# ADCSHub.net
KiCad netlist of a schematic drawn in Altium Designer
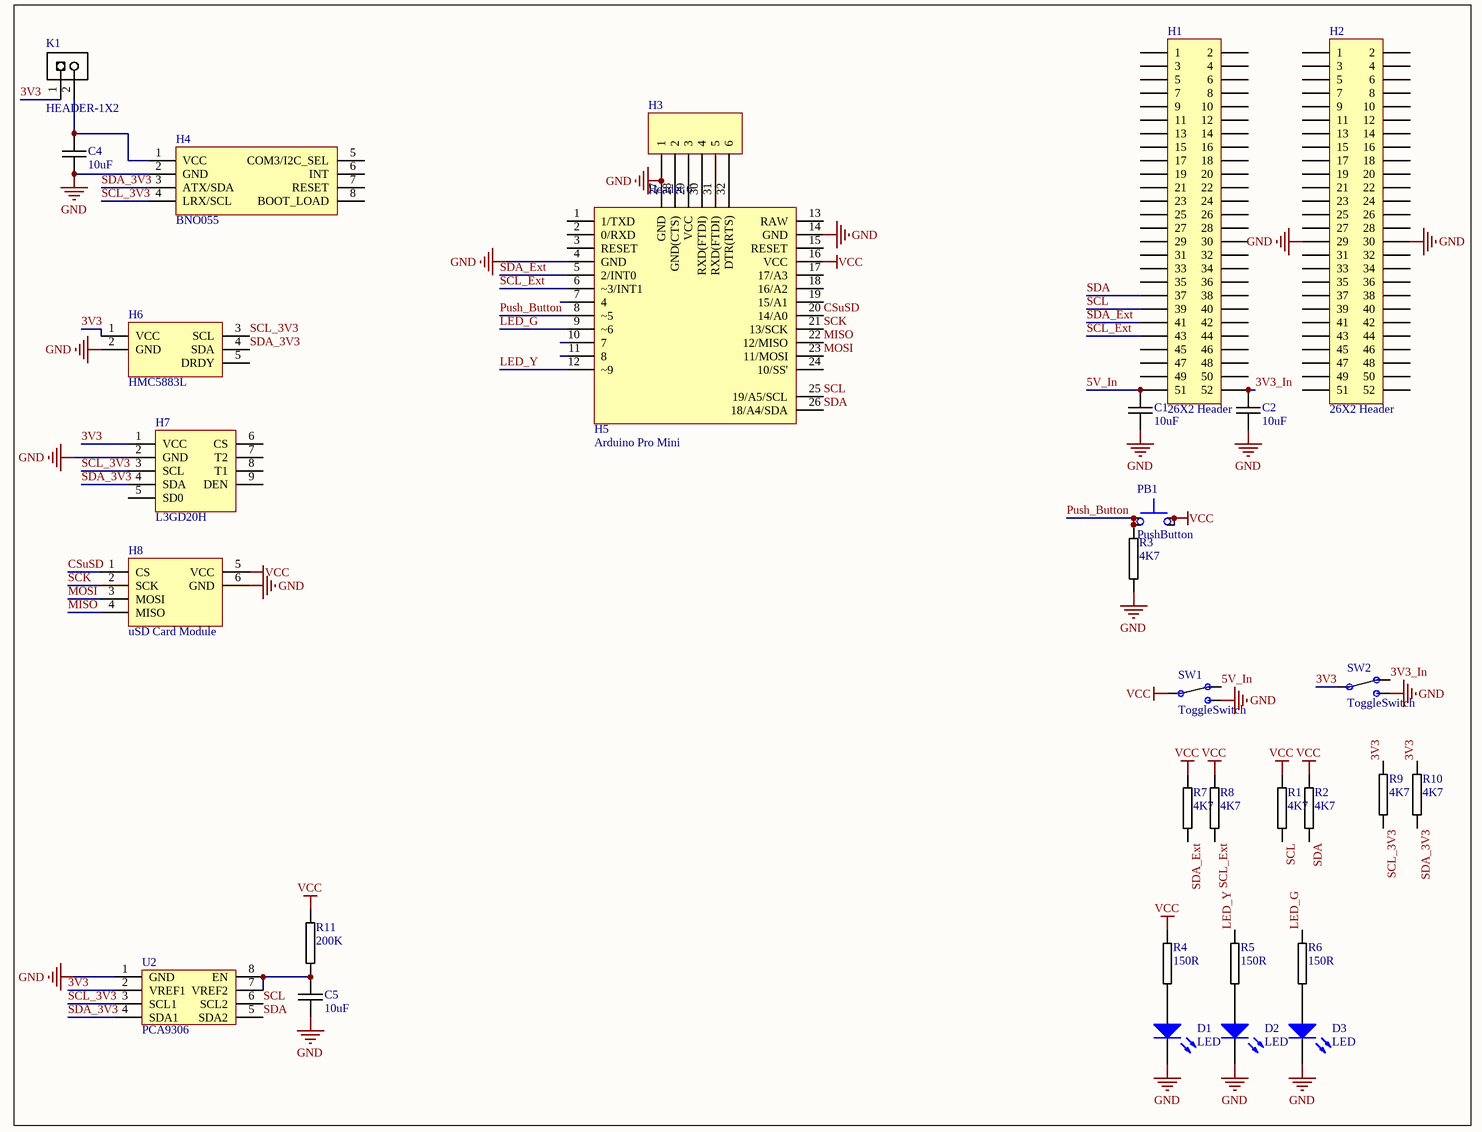
[diagram p0: ADCSHub.SchDoc]

(export (version "E")
  (design (tool "Eeschema 10.0.6"))
  (components
    (comp (ref "C1")
      (value "10uF")
      (footprint "0805C-TBD")
      (description "CAPACITOR 0805 CERAMIC")
      (libsource (lib "vh_altium_library") (part "0805C-100nF-25V-X7R-MUR"))
    )
    (comp (ref "C2")
      (value "10uF")
      (footprint "0805C-TBD")
      (description "CAPACITOR 0805 CERAMIC")
      (libsource (lib "vh_altium_library") (part "0805C-100nF-25V-X7R-MUR"))
    )
    (comp (ref "C4")
      (value "10uF")
      (footprint "0805C-GENERIC")
      (description "CAPACITOR 0805 CERAMIC")
      (fields
        (field (name "MANUFACTURER PART NUMBER") "C2012X5R1C106M")
        (field (name "MANUFACTURER") "TDK Corporation")
      )
      (libsource (lib "vh_altium_library") (part "0805C-10UF-16V-X5R-TDK"))
    )
    (comp (ref "C5")
      (value "10uF")
      (footprint "0805C-GENERIC")
      (description "CAPACITOR 0805 CERAMIC")
      (fields
        (field (name "MANUFACTURER PART NUMBER") "C2012X5R1C106M")
        (field (name "MANUFACTURER") "TDK Corporation")
      )
      (libsource (lib "vh_altium_library") (part "0805C-10UF-16V-X5R-TDK"))
    )
    (comp (ref "D1")
      (value "LED")
      (footprint "LED")
      (description "Small LED")
      (libsource (lib "Components") (part "LED"))
    )
    (comp (ref "D2")
      (value "LED")
      (footprint "LED")
      (description "Small LED")
      (libsource (lib "Components") (part "LED"))
    )
    (comp (ref "D3")
      (value "LED")
      (footprint "LED")
      (description "Small LED")
      (libsource (lib "Components") (part "LED"))
    )
    (comp (ref "H1")
      (value "26X2 Header")
      (footprint "26X2 Header")
      (libsource (lib "CustomParts") (part "26X2 Header"))
    )
    (comp (ref "H2")
      (value "26X2 Header")
      (footprint "26X2 Header")
      (libsource (lib "CustomParts") (part "26X2 Header"))
    )
    (comp (ref "H3")
      (value "Header 6")
      (footprint "HDR1X6")
      (description "Header, 6-Pin")
      (fields (field (name "PUBLISHER") "Altium Limited"))
      (libsource (lib "Miscellaneous Connectors") (part "Header 6"))
    )
    (comp (ref "H4")
      (value "BNO055")
      (footprint "BNO055")
      (description "Accel+Gyro+Mag")
      (libsource (lib "Components") (part "BNO055"))
    )
    (comp (ref "H5")
      (value "Arduino Pro Mini")
      (footprint "Arduino Pro Mini")
      (libsource (lib "Components") (part "Arduino Pro Mini"))
    )
    (comp (ref "H6")
      (value "HMC5883L")
      (footprint "HMC5883L")
      (description "Magnetometer")
      (libsource (lib "Components") (part "HMC5883L"))
    )
    (comp (ref "H7")
      (value "L3GD20H")
      (footprint "L3GD20H")
      (description "Gyroscope")
      (libsource (lib "Components") (part "L3GD20H"))
    )
    (comp (ref "H8")
      (value "uSD Card Module")
      (footprint "uSD Card Module")
      (libsource (lib "Components") (part "uSD Card Module"))
    )
    (comp (ref "K1")
      (value "HEADER-1X2")
      (footprint "HEADER-1X2")
      (libsource (lib "vh_altium_library") (part "HEADER-1X2"))
    )
    (comp (ref "PB1")
      (value "PushButton")
      (footprint "PushButton")
      (libsource (lib "SBv1Components") (part "PushButton"))
    )
    (comp (ref "R1")
      (value "4K7")
      (footprint "0805R-4K7")
      (description "RESISTOR 0805 1/4 WATT THIN FILM")
      (libsource (lib "vh_altium_library") (part "0805R-4K7"))
    )
    (comp (ref "R2")
      (value "4K7")
      (footprint "0805R-4K7")
      (description "RESISTOR 0805 1/4 WATT THIN FILM")
      (libsource (lib "vh_altium_library") (part "0805R-4K7"))
    )
    (comp (ref "R3")
      (value "4K7")
      (footprint "0805R-4K7")
      (description "RESISTOR 0805 1/4 WATT THIN FILM")
      (libsource (lib "vh_altium_library") (part "0805R-4K7"))
    )
    (comp (ref "R4")
      (value "150R")
      (footprint "0805R-150")
      (description "RESISTOR 0805 1/4 WATT THIN FILM")
      (libsource (lib "vh_altium_library") (part "0805R-150"))
    )
    (comp (ref "R5")
      (value "150R")
      (footprint "0805R-150")
      (description "RESISTOR 0805 1/4 WATT THIN FILM")
      (libsource (lib "vh_altium_library") (part "0805R-150"))
    )
    (comp (ref "R6")
      (value "150R")
      (footprint "0805R-150")
      (description "RESISTOR 0805 1/4 WATT THIN FILM")
      (libsource (lib "vh_altium_library") (part "0805R-150"))
    )
    (comp (ref "R7")
      (value "4K7")
      (footprint "0805R-4K7")
      (description "RESISTOR 0805 1/4 WATT THIN FILM")
      (libsource (lib "vh_altium_library") (part "0805R-4K7"))
    )
    (comp (ref "R8")
      (value "4K7")
      (footprint "0805R-4K7")
      (description "RESISTOR 0805 1/4 WATT THIN FILM")
      (libsource (lib "vh_altium_library") (part "0805R-4K7"))
    )
    (comp (ref "R9")
      (value "4K7")
      (footprint "0805R-4K7")
      (description "RESISTOR 0805 1/4 WATT THIN FILM")
      (libsource (lib "vh_altium_library") (part "0805R-4K7"))
    )
    (comp (ref "R10")
      (value "4K7")
      (footprint "0805R-4K7")
      (description "RESISTOR 0805 1/4 WATT THIN FILM")
      (libsource (lib "vh_altium_library") (part "0805R-4K7"))
    )
    (comp (ref "R11")
      (value "200K")
      (footprint "0805R-4K7")
      (description "RESISTOR 0805 1/4 WATT THIN FILM")
      (libsource (lib "vh_altium_library") (part "0805R-4K7"))
    )
    (comp (ref "SW1")
      (value "ToggleSwitch")
      (footprint "SWITCHFOOTPRINT")
      (libsource (lib "SBv1Components") (part "ToggleSwitch"))
    )
    (comp (ref "SW2")
      (value "ToggleSwitch")
      (footprint "SWITCHFOOTPRINT")
      (libsource (lib "SBv1Components") (part "ToggleSwitch"))
    )
    (comp (ref "U2")
      (value "PCA9306")
      (footprint "PCA9306")
      (description "Dual Bidirectional I2C Voltage Level Translator")
      (libsource (lib "Components") (part "PCA9306"))
    )
  )
  (nets
    (net (code "1") (name "/3V3") (class "Default")
      (node (ref "H6") (pin "1") (pinfunction "VCC_1") (pintype "passive"))
      (node (ref "H7") (pin "1") (pinfunction "VCC_1") (pintype "passive"))
      (node (ref "K1") (pin "1") (pintype "passive"))
      (node (ref "R10") (pin "1") (pintype "passive"))
      (node (ref "R9") (pin "1") (pintype "passive"))
      (node (ref "SW2") (pin "23") (pinfunction "23_23") (pintype "passive"))
      (node (ref "U2") (pin "2") (pinfunction "VREF1_2") (pintype "passive"))
    )
    (net (code "2") (name "/3V3_In") (class "Default")
      (node (ref "C2") (pin "1") (pintype "passive"))
      (node (ref "H1") (pin "52") (pinfunction "52_52") (pintype "passive"))
      (node (ref "SW2") (pin "24") (pinfunction "24_24") (pintype "passive"))
    )
    (net (code "3") (name "/5V_In") (class "Default")
      (node (ref "C1") (pin "1") (pintype "passive"))
      (node (ref "H1") (pin "51") (pinfunction "51_51") (pintype "passive"))
      (node (ref "SW1") (pin "24") (pinfunction "24_24") (pintype "passive"))
    )
    (net (code "4") (name "/CSuSD") (class "Default")
      (node (ref "H5") (pin "20") (pinfunction "14/A0_20") (pintype "passive"))
      (node (ref "H8") (pin "1") (pinfunction "CS_1") (pintype "passive"))
    )
    (net (code "5") (name "/LED_G") (class "Default")
      (node (ref "H5") (pin "9") (pinfunction "~6_9") (pintype "passive"))
      (node (ref "R6") (pin "1") (pintype "passive"))
    )
    (net (code "6") (name "/LED_Y") (class "Default")
      (node (ref "H5") (pin "12") (pinfunction "~9_12") (pintype "passive"))
      (node (ref "R5") (pin "1") (pintype "passive"))
    )
    (net (code "7") (name "/MISO") (class "Default")
      (node (ref "H5") (pin "22") (pinfunction "12/MISO_22") (pintype "passive"))
      (node (ref "H8") (pin "4") (pinfunction "MISO_4") (pintype "passive"))
    )
    (net (code "8") (name "/MOSI") (class "Default")
      (node (ref "H5") (pin "23") (pinfunction "11/MOSI_23") (pintype "passive"))
      (node (ref "H8") (pin "3") (pinfunction "MOSI_3") (pintype "passive"))
    )
    (net (code "9") (name "/Push_Button") (class "Default")
      (node (ref "H5") (pin "8") (pinfunction "~5_8") (pintype "passive"))
      (node (ref "PB1") (pin "26") (pinfunction "26_26") (pintype "passive"))
      (node (ref "PB1") (pin "28") (pinfunction "28_28") (pintype "passive"))
      (node (ref "R3") (pin "1") (pintype "passive"))
    )
    (net (code "10") (name "/SCK") (class "Default")
      (node (ref "H5") (pin "21") (pinfunction "13/SCK_21") (pintype "passive"))
      (node (ref "H8") (pin "2") (pinfunction "SCK_2") (pintype "passive"))
    )
    (net (code "11") (name "/SCL") (class "Default")
      (node (ref "H1") (pin "39") (pinfunction "39_39") (pintype "passive"))
      (node (ref "H5") (pin "25") (pinfunction "19/A5/SCL_25") (pintype "passive"))
      (node (ref "R1") (pin "2") (pintype "passive"))
      (node (ref "U2") (pin "6") (pinfunction "SCL2_6") (pintype "passive"))
    )
    (net (code "12") (name "/SCL_3V3") (class "Default")
      (node (ref "H4") (pin "4") (pinfunction "LRX/SCL_4") (pintype "passive"))
      (node (ref "H6") (pin "3") (pinfunction "SCL_3") (pintype "passive"))
      (node (ref "H7") (pin "3") (pinfunction "SCL_3") (pintype "passive"))
      (node (ref "R9") (pin "2") (pintype "passive"))
      (node (ref "U2") (pin "3") (pinfunction "SCL1_3") (pintype "passive"))
    )
    (net (code "13") (name "/SCL_Ext") (class "Default")
      (node (ref "H1") (pin "43") (pinfunction "43_43") (pintype "passive"))
      (node (ref "H5") (pin "6") (pinfunction "~3/INT1_6") (pintype "passive"))
      (node (ref "R8") (pin "2") (pintype "passive"))
    )
    (net (code "14") (name "/SDA") (class "Default")
      (node (ref "H1") (pin "37") (pinfunction "37_37") (pintype "passive"))
      (node (ref "H5") (pin "26") (pinfunction "18/A4/SDA_26") (pintype "passive"))
      (node (ref "R2") (pin "2") (pintype "passive"))
      (node (ref "U2") (pin "5") (pinfunction "SDA2_5") (pintype "passive"))
    )
    (net (code "15") (name "/SDA_3V3") (class "Default")
      (node (ref "H4") (pin "3") (pinfunction "ATX/SDA_3") (pintype "passive"))
      (node (ref "H6") (pin "4") (pinfunction "SDA_4") (pintype "passive"))
      (node (ref "H7") (pin "4") (pinfunction "SDA_4") (pintype "passive"))
      (node (ref "R10") (pin "2") (pintype "passive"))
      (node (ref "U2") (pin "4") (pinfunction "SDA1_4") (pintype "passive"))
    )
    (net (code "16") (name "/SDA_Ext") (class "Default")
      (node (ref "H1") (pin "41") (pinfunction "41_41") (pintype "passive"))
      (node (ref "H5") (pin "5") (pinfunction "2/INT0_5") (pintype "passive"))
      (node (ref "R7") (pin "2") (pintype "passive"))
    )
    (net (code "17") (name "GND") (class "Default")
      (node (ref "C1") (pin "2") (pintype "passive"))
      (node (ref "C2") (pin "2") (pintype "passive"))
      (node (ref "C4") (pin "2") (pintype "passive"))
      (node (ref "C5") (pin "2") (pintype "passive"))
      (node (ref "D1") (pin "2") (pinfunction "K_2") (pintype "passive"))
      (node (ref "D2") (pin "2") (pinfunction "K_2") (pintype "passive"))
      (node (ref "D3") (pin "2") (pinfunction "K_2") (pintype "passive"))
      (node (ref "H2") (pin "29") (pinfunction "29_29") (pintype "passive"))
      (node (ref "H2") (pin "30") (pinfunction "30_30") (pintype "passive"))
      (node (ref "H3") (pin "1") (pinfunction "1_1") (pintype "passive"))
      (node (ref "H4") (pin "2") (pinfunction "GND_2") (pintype "passive"))
      (node (ref "H5") (pin "14") (pinfunction "GND_14") (pintype "passive"))
      (node (ref "H5") (pin "27") (pinfunction "GND_27") (pintype "passive"))
      (node (ref "H5") (pin "4") (pinfunction "GND_4") (pintype "passive"))
      (node (ref "H6") (pin "2") (pinfunction "GND_2") (pintype "passive"))
      (node (ref "H7") (pin "2") (pinfunction "GND_2") (pintype "passive"))
      (node (ref "H8") (pin "6") (pinfunction "GND_6") (pintype "passive"))
      (node (ref "R3") (pin "2") (pintype "passive"))
      (node (ref "SW1") (pin "25") (pinfunction "25_25") (pintype "passive"))
      (node (ref "SW2") (pin "25") (pinfunction "25_25") (pintype "passive"))
      (node (ref "U2") (pin "1") (pinfunction "GND_1") (pintype "passive"))
    )
    (net (code "18") (name "Net-(D1-A)") (class "Default")
      (node (ref "D1") (pin "1") (pinfunction "A_1") (pintype "passive"))
      (node (ref "R4") (pin "2") (pintype "passive"))
    )
    (net (code "19") (name "Net-(D2-A)") (class "Default")
      (node (ref "D2") (pin "1") (pinfunction "A_1") (pintype "passive"))
      (node (ref "R5") (pin "2") (pintype "passive"))
    )
    (net (code "20") (name "Net-(D3-A)") (class "Default")
      (node (ref "D3") (pin "1") (pinfunction "A_1") (pintype "passive"))
      (node (ref "R6") (pin "2") (pintype "passive"))
    )
    (net (code "21") (name "Net-(H3-Pad3)") (class "Default")
      (node (ref "H3") (pin "3") (pinfunction "3_3") (pintype "passive"))
      (node (ref "H5") (pin "29") (pinfunction "VCC_29") (pintype "passive"))
    )
    (net (code "22") (name "Net-(H3-Pad4)") (class "Default")
      (node (ref "H3") (pin "4") (pinfunction "4_4") (pintype "passive"))
      (node (ref "H5") (pin "30") (pinfunction "RXD(FTDI)_30") (pintype "passive"))
    )
    (net (code "23") (name "Net-(H3-Pad5)") (class "Default")
      (node (ref "H3") (pin "5") (pinfunction "5_5") (pintype "passive"))
      (node (ref "H5") (pin "31") (pinfunction "RXD(FTDI)_31") (pintype "passive"))
    )
    (net (code "24") (name "Net-(H4-VCC)") (class "Default")
      (node (ref "C4") (pin "1") (pintype "passive"))
      (node (ref "H4") (pin "1") (pinfunction "VCC_1") (pintype "passive"))
      (node (ref "K1") (pin "2") (pintype "passive"))
    )
    (net (code "25") (name "Net-(H5-DTR(RTS))") (class "Default")
      (node (ref "H3") (pin "6") (pinfunction "6_6") (pintype "passive"))
      (node (ref "H5") (pin "32") (pinfunction "DTR(RTS)_32") (pintype "passive"))
    )
    (net (code "26") (name "Net-(H5-GND(CTS))") (class "Default")
      (node (ref "H3") (pin "2") (pinfunction "2_2") (pintype "passive"))
      (node (ref "H5") (pin "28") (pinfunction "GND(CTS)_28") (pintype "passive"))
    )
    (net (code "27") (name "Net-(U2-EN)") (class "Default")
      (node (ref "C5") (pin "1") (pintype "passive"))
      (node (ref "R11") (pin "1") (pintype "passive"))
      (node (ref "U2") (pin "7") (pinfunction "VREF2_7") (pintype "passive"))
      (node (ref "U2") (pin "8") (pinfunction "EN_8") (pintype "passive"))
    )
    (net (code "28") (name "VCC") (class "Default")
      (node (ref "H5") (pin "16") (pinfunction "VCC_16") (pintype "passive"))
      (node (ref "H8") (pin "5") (pinfunction "VCC_5") (pintype "passive"))
      (node (ref "PB1") (pin "27") (pinfunction "27_27") (pintype "passive"))
      (node (ref "PB1") (pin "29") (pinfunction "29_29") (pintype "passive"))
      (node (ref "R1") (pin "1") (pintype "passive"))
      (node (ref "R11") (pin "2") (pintype "passive"))
      (node (ref "R2") (pin "1") (pintype "passive"))
      (node (ref "R4") (pin "1") (pintype "passive"))
      (node (ref "R7") (pin "1") (pintype "passive"))
      (node (ref "R8") (pin "1") (pintype "passive"))
      (node (ref "SW1") (pin "23") (pinfunction "23_23") (pintype "passive"))
    )
    (net (code "29") (name "unconnected-(H1-Pad1)") (class "Default")
      (node (ref "H1") (pin "1") (pinfunction "1_1") (pintype "passive"))
    )
    (net (code "30") (name "unconnected-(H1-Pad2)") (class "Default")
      (node (ref "H1") (pin "2") (pinfunction "2_2") (pintype "passive"))
    )
    (net (code "31") (name "unconnected-(H1-Pad3)") (class "Default")
      (node (ref "H1") (pin "3") (pinfunction "3_3") (pintype "passive"))
    )
    (net (code "32") (name "unconnected-(H1-Pad4)") (class "Default")
      (node (ref "H1") (pin "4") (pinfunction "4_4") (pintype "passive"))
    )
    (net (code "33") (name "unconnected-(H1-Pad5)") (class "Default")
      (node (ref "H1") (pin "5") (pinfunction "5_5") (pintype "passive"))
    )
    (net (code "34") (name "unconnected-(H1-Pad6)") (class "Default")
      (node (ref "H1") (pin "6") (pinfunction "6_6") (pintype "passive"))
    )
    (net (code "35") (name "unconnected-(H1-Pad7)") (class "Default")
      (node (ref "H1") (pin "7") (pinfunction "7_7") (pintype "passive"))
    )
    (net (code "36") (name "unconnected-(H1-Pad8)") (class "Default")
      (node (ref "H1") (pin "8") (pinfunction "8_8") (pintype "passive"))
    )
    (net (code "37") (name "unconnected-(H1-Pad9)") (class "Default")
      (node (ref "H1") (pin "9") (pinfunction "9_9") (pintype "passive"))
    )
    (net (code "38") (name "unconnected-(H1-Pad10)") (class "Default")
      (node (ref "H1") (pin "10") (pinfunction "10_10") (pintype "passive"))
    )
    (net (code "39") (name "unconnected-(H1-Pad11)") (class "Default")
      (node (ref "H1") (pin "11") (pinfunction "11_11") (pintype "passive"))
    )
    (net (code "40") (name "unconnected-(H1-Pad12)") (class "Default")
      (node (ref "H1") (pin "12") (pinfunction "12_12") (pintype "passive"))
    )
    (net (code "41") (name "unconnected-(H1-Pad13)") (class "Default")
      (node (ref "H1") (pin "13") (pinfunction "13_13") (pintype "passive"))
    )
    (net (code "42") (name "unconnected-(H1-Pad14)") (class "Default")
      (node (ref "H1") (pin "14") (pinfunction "14_14") (pintype "passive"))
    )
    (net (code "43") (name "unconnected-(H1-Pad15)") (class "Default")
      (node (ref "H1") (pin "15") (pinfunction "15_15") (pintype "passive"))
    )
    (net (code "44") (name "unconnected-(H1-Pad16)") (class "Default")
      (node (ref "H1") (pin "16") (pinfunction "16_16") (pintype "passive"))
    )
    (net (code "45") (name "unconnected-(H1-Pad17)") (class "Default")
      (node (ref "H1") (pin "17") (pinfunction "17_17") (pintype "passive"))
    )
    (net (code "46") (name "unconnected-(H1-Pad18)") (class "Default")
      (node (ref "H1") (pin "18") (pinfunction "18_18") (pintype "passive"))
    )
    (net (code "47") (name "unconnected-(H1-Pad19)") (class "Default")
      (node (ref "H1") (pin "19") (pinfunction "19_19") (pintype "passive"))
    )
    (net (code "48") (name "unconnected-(H1-Pad20)") (class "Default")
      (node (ref "H1") (pin "20") (pinfunction "20_20") (pintype "passive"))
    )
    (net (code "49") (name "unconnected-(H1-Pad21)") (class "Default")
      (node (ref "H1") (pin "21") (pinfunction "21_21") (pintype "passive"))
    )
    (net (code "50") (name "unconnected-(H1-Pad22)") (class "Default")
      (node (ref "H1") (pin "22") (pinfunction "22_22") (pintype "passive"))
    )
    (net (code "51") (name "unconnected-(H1-Pad23)") (class "Default")
      (node (ref "H1") (pin "23") (pinfunction "23_23") (pintype "passive"))
    )
    (net (code "52") (name "unconnected-(H1-Pad24)") (class "Default")
      (node (ref "H1") (pin "24") (pinfunction "24_24") (pintype "passive"))
    )
    (net (code "53") (name "unconnected-(H1-Pad25)") (class "Default")
      (node (ref "H1") (pin "25") (pinfunction "25_25") (pintype "passive"))
    )
    (net (code "54") (name "unconnected-(H1-Pad26)") (class "Default")
      (node (ref "H1") (pin "26") (pinfunction "26_26") (pintype "passive"))
    )
    (net (code "55") (name "unconnected-(H1-Pad27)") (class "Default")
      (node (ref "H1") (pin "27") (pinfunction "27_27") (pintype "passive"))
    )
    (net (code "56") (name "unconnected-(H1-Pad28)") (class "Default")
      (node (ref "H1") (pin "28") (pinfunction "28_28") (pintype "passive"))
    )
    (net (code "57") (name "unconnected-(H1-Pad29)") (class "Default")
      (node (ref "H1") (pin "29") (pinfunction "29_29") (pintype "passive"))
    )
    (net (code "58") (name "unconnected-(H1-Pad30)") (class "Default")
      (node (ref "H1") (pin "30") (pinfunction "30_30") (pintype "passive"))
    )
    (net (code "59") (name "unconnected-(H1-Pad31)") (class "Default")
      (node (ref "H1") (pin "31") (pinfunction "31_31") (pintype "passive"))
    )
    (net (code "60") (name "unconnected-(H1-Pad32)") (class "Default")
      (node (ref "H1") (pin "32") (pinfunction "32_32") (pintype "passive"))
    )
    (net (code "61") (name "unconnected-(H1-Pad33)") (class "Default")
      (node (ref "H1") (pin "33") (pinfunction "33_33") (pintype "passive"))
    )
    (net (code "62") (name "unconnected-(H1-Pad34)") (class "Default")
      (node (ref "H1") (pin "34") (pinfunction "34_34") (pintype "passive"))
    )
    (net (code "63") (name "unconnected-(H1-Pad35)") (class "Default")
      (node (ref "H1") (pin "35") (pinfunction "35_35") (pintype "passive"))
    )
    (net (code "64") (name "unconnected-(H1-Pad36)") (class "Default")
      (node (ref "H1") (pin "36") (pinfunction "36_36") (pintype "passive"))
    )
    (net (code "65") (name "unconnected-(H1-Pad38)") (class "Default")
      (node (ref "H1") (pin "38") (pinfunction "38_38") (pintype "passive"))
    )
    (net (code "66") (name "unconnected-(H1-Pad40)") (class "Default")
      (node (ref "H1") (pin "40") (pinfunction "40_40") (pintype "passive"))
    )
    (net (code "67") (name "unconnected-(H1-Pad42)") (class "Default")
      (node (ref "H1") (pin "42") (pinfunction "42_42") (pintype "passive"))
    )
    (net (code "68") (name "unconnected-(H1-Pad44)") (class "Default")
      (node (ref "H1") (pin "44") (pinfunction "44_44") (pintype "passive"))
    )
    (net (code "69") (name "unconnected-(H1-Pad45)") (class "Default")
      (node (ref "H1") (pin "45") (pinfunction "45_45") (pintype "passive"))
    )
    (net (code "70") (name "unconnected-(H1-Pad46)") (class "Default")
      (node (ref "H1") (pin "46") (pinfunction "46_46") (pintype "passive"))
    )
    (net (code "71") (name "unconnected-(H1-Pad47)") (class "Default")
      (node (ref "H1") (pin "47") (pinfunction "47_47") (pintype "passive"))
    )
    (net (code "72") (name "unconnected-(H1-Pad48)") (class "Default")
      (node (ref "H1") (pin "48") (pinfunction "48_48") (pintype "passive"))
    )
    (net (code "73") (name "unconnected-(H1-Pad49)") (class "Default")
      (node (ref "H1") (pin "49") (pinfunction "49_49") (pintype "passive"))
    )
    (net (code "74") (name "unconnected-(H1-Pad50)") (class "Default")
      (node (ref "H1") (pin "50") (pinfunction "50_50") (pintype "passive"))
    )
    (net (code "75") (name "unconnected-(H2-Pad1)") (class "Default")
      (node (ref "H2") (pin "1") (pinfunction "1_1") (pintype "passive"))
    )
    (net (code "76") (name "unconnected-(H2-Pad2)") (class "Default")
      (node (ref "H2") (pin "2") (pinfunction "2_2") (pintype "passive"))
    )
    (net (code "77") (name "unconnected-(H2-Pad3)") (class "Default")
      (node (ref "H2") (pin "3") (pinfunction "3_3") (pintype "passive"))
    )
    (net (code "78") (name "unconnected-(H2-Pad4)") (class "Default")
      (node (ref "H2") (pin "4") (pinfunction "4_4") (pintype "passive"))
    )
    (net (code "79") (name "unconnected-(H2-Pad5)") (class "Default")
      (node (ref "H2") (pin "5") (pinfunction "5_5") (pintype "passive"))
    )
    (net (code "80") (name "unconnected-(H2-Pad6)") (class "Default")
      (node (ref "H2") (pin "6") (pinfunction "6_6") (pintype "passive"))
    )
    (net (code "81") (name "unconnected-(H2-Pad7)") (class "Default")
      (node (ref "H2") (pin "7") (pinfunction "7_7") (pintype "passive"))
    )
    (net (code "82") (name "unconnected-(H2-Pad8)") (class "Default")
      (node (ref "H2") (pin "8") (pinfunction "8_8") (pintype "passive"))
    )
    (net (code "83") (name "unconnected-(H2-Pad9)") (class "Default")
      (node (ref "H2") (pin "9") (pinfunction "9_9") (pintype "passive"))
    )
    (net (code "84") (name "unconnected-(H2-Pad10)") (class "Default")
      (node (ref "H2") (pin "10") (pinfunction "10_10") (pintype "passive"))
    )
    (net (code "85") (name "unconnected-(H2-Pad11)") (class "Default")
      (node (ref "H2") (pin "11") (pinfunction "11_11") (pintype "passive"))
    )
    (net (code "86") (name "unconnected-(H2-Pad12)") (class "Default")
      (node (ref "H2") (pin "12") (pinfunction "12_12") (pintype "passive"))
    )
    (net (code "87") (name "unconnected-(H2-Pad13)") (class "Default")
      (node (ref "H2") (pin "13") (pinfunction "13_13") (pintype "passive"))
    )
    (net (code "88") (name "unconnected-(H2-Pad14)") (class "Default")
      (node (ref "H2") (pin "14") (pinfunction "14_14") (pintype "passive"))
    )
    (net (code "89") (name "unconnected-(H2-Pad15)") (class "Default")
      (node (ref "H2") (pin "15") (pinfunction "15_15") (pintype "passive"))
    )
    (net (code "90") (name "unconnected-(H2-Pad16)") (class "Default")
      (node (ref "H2") (pin "16") (pinfunction "16_16") (pintype "passive"))
    )
    (net (code "91") (name "unconnected-(H2-Pad17)") (class "Default")
      (node (ref "H2") (pin "17") (pinfunction "17_17") (pintype "passive"))
    )
    (net (code "92") (name "unconnected-(H2-Pad18)") (class "Default")
      (node (ref "H2") (pin "18") (pinfunction "18_18") (pintype "passive"))
    )
    (net (code "93") (name "unconnected-(H2-Pad19)") (class "Default")
      (node (ref "H2") (pin "19") (pinfunction "19_19") (pintype "passive"))
    )
    (net (code "94") (name "unconnected-(H2-Pad20)") (class "Default")
      (node (ref "H2") (pin "20") (pinfunction "20_20") (pintype "passive"))
    )
    (net (code "95") (name "unconnected-(H2-Pad21)") (class "Default")
      (node (ref "H2") (pin "21") (pinfunction "21_21") (pintype "passive"))
    )
    (net (code "96") (name "unconnected-(H2-Pad22)") (class "Default")
      (node (ref "H2") (pin "22") (pinfunction "22_22") (pintype "passive"))
    )
    (net (code "97") (name "unconnected-(H2-Pad23)") (class "Default")
      (node (ref "H2") (pin "23") (pinfunction "23_23") (pintype "passive"))
    )
    (net (code "98") (name "unconnected-(H2-Pad24)") (class "Default")
      (node (ref "H2") (pin "24") (pinfunction "24_24") (pintype "passive"))
    )
    (net (code "99") (name "unconnected-(H2-Pad25)") (class "Default")
      (node (ref "H2") (pin "25") (pinfunction "25_25") (pintype "passive"))
    )
    (net (code "100") (name "unconnected-(H2-Pad26)") (class "Default")
      (node (ref "H2") (pin "26") (pinfunction "26_26") (pintype "passive"))
    )
    (net (code "101") (name "unconnected-(H2-Pad27)") (class "Default")
      (node (ref "H2") (pin "27") (pinfunction "27_27") (pintype "passive"))
    )
    (net (code "102") (name "unconnected-(H2-Pad28)") (class "Default")
      (node (ref "H2") (pin "28") (pinfunction "28_28") (pintype "passive"))
    )
    (net (code "103") (name "unconnected-(H2-Pad31)") (class "Default")
      (node (ref "H2") (pin "31") (pinfunction "31_31") (pintype "passive"))
    )
    (net (code "104") (name "unconnected-(H2-Pad32)") (class "Default")
      (node (ref "H2") (pin "32") (pinfunction "32_32") (pintype "passive"))
    )
    (net (code "105") (name "unconnected-(H2-Pad33)") (class "Default")
      (node (ref "H2") (pin "33") (pinfunction "33_33") (pintype "passive"))
    )
    (net (code "106") (name "unconnected-(H2-Pad34)") (class "Default")
      (node (ref "H2") (pin "34") (pinfunction "34_34") (pintype "passive"))
    )
    (net (code "107") (name "unconnected-(H2-Pad35)") (class "Default")
      (node (ref "H2") (pin "35") (pinfunction "35_35") (pintype "passive"))
    )
    (net (code "108") (name "unconnected-(H2-Pad36)") (class "Default")
      (node (ref "H2") (pin "36") (pinfunction "36_36") (pintype "passive"))
    )
    (net (code "109") (name "unconnected-(H2-Pad37)") (class "Default")
      (node (ref "H2") (pin "37") (pinfunction "37_37") (pintype "passive"))
    )
    (net (code "110") (name "unconnected-(H2-Pad38)") (class "Default")
      (node (ref "H2") (pin "38") (pinfunction "38_38") (pintype "passive"))
    )
    (net (code "111") (name "unconnected-(H2-Pad39)") (class "Default")
      (node (ref "H2") (pin "39") (pinfunction "39_39") (pintype "passive"))
    )
    (net (code "112") (name "unconnected-(H2-Pad40)") (class "Default")
      (node (ref "H2") (pin "40") (pinfunction "40_40") (pintype "passive"))
    )
    (net (code "113") (name "unconnected-(H2-Pad41)") (class "Default")
      (node (ref "H2") (pin "41") (pinfunction "41_41") (pintype "passive"))
    )
    (net (code "114") (name "unconnected-(H2-Pad42)") (class "Default")
      (node (ref "H2") (pin "42") (pinfunction "42_42") (pintype "passive"))
    )
    (net (code "115") (name "unconnected-(H2-Pad43)") (class "Default")
      (node (ref "H2") (pin "43") (pinfunction "43_43") (pintype "passive"))
    )
    (net (code "116") (name "unconnected-(H2-Pad44)") (class "Default")
      (node (ref "H2") (pin "44") (pinfunction "44_44") (pintype "passive"))
    )
    (net (code "117") (name "unconnected-(H2-Pad45)") (class "Default")
      (node (ref "H2") (pin "45") (pinfunction "45_45") (pintype "passive"))
    )
    (net (code "118") (name "unconnected-(H2-Pad46)") (class "Default")
      (node (ref "H2") (pin "46") (pinfunction "46_46") (pintype "passive"))
    )
    (net (code "119") (name "unconnected-(H2-Pad47)") (class "Default")
      (node (ref "H2") (pin "47") (pinfunction "47_47") (pintype "passive"))
    )
    (net (code "120") (name "unconnected-(H2-Pad48)") (class "Default")
      (node (ref "H2") (pin "48") (pinfunction "48_48") (pintype "passive"))
    )
    (net (code "121") (name "unconnected-(H2-Pad49)") (class "Default")
      (node (ref "H2") (pin "49") (pinfunction "49_49") (pintype "passive"))
    )
    (net (code "122") (name "unconnected-(H2-Pad50)") (class "Default")
      (node (ref "H2") (pin "50") (pinfunction "50_50") (pintype "passive"))
    )
    (net (code "123") (name "unconnected-(H2-Pad51)") (class "Default")
      (node (ref "H2") (pin "51") (pinfunction "51_51") (pintype "passive"))
    )
    (net (code "124") (name "unconnected-(H2-Pad52)") (class "Default")
      (node (ref "H2") (pin "52") (pinfunction "52_52") (pintype "passive"))
    )
    (net (code "125") (name "unconnected-(H4-BOOT_LOAD-Pad8)") (class "Default")
      (node (ref "H4") (pin "8") (pinfunction "BOOT_LOAD_8") (pintype "passive"))
    )
    (net (code "126") (name "unconnected-(H4-COM3{slash}I2C_SEL-Pad5)") (class "Default")
      (node (ref "H4") (pin "5") (pinfunction "COM3/I2C_SEL_5") (pintype "passive"))
    )
    (net (code "127") (name "unconnected-(H4-INT-Pad6)") (class "Default")
      (node (ref "H4") (pin "6") (pinfunction "INT_6") (pintype "passive"))
    )
    (net (code "128") (name "unconnected-(H4-RESET-Pad7)") (class "Default")
      (node (ref "H4") (pin "7") (pinfunction "RESET_7") (pintype "passive"))
    )
    (net (code "129") (name "unconnected-(H5-0{slash}RXD-Pad2)") (class "Default")
      (node (ref "H5") (pin "2") (pinfunction "0/RXD_2") (pintype "passive"))
    )
    (net (code "130") (name "unconnected-(H5-1{slash}TXD-Pad1)") (class "Default")
      (node (ref "H5") (pin "1") (pinfunction "1/TXD_1") (pintype "passive"))
    )
    (net (code "131") (name "unconnected-(H5-4-Pad7)") (class "Default")
      (node (ref "H5") (pin "7") (pinfunction "4_7") (pintype "passive"))
    )
    (net (code "132") (name "unconnected-(H5-7-Pad10)") (class "Default")
      (node (ref "H5") (pin "10") (pinfunction "7_10") (pintype "passive"))
    )
    (net (code "133") (name "unconnected-(H5-8-Pad11)") (class "Default")
      (node (ref "H5") (pin "11") (pinfunction "8_11") (pintype "passive"))
    )
    (net (code "134") (name "unconnected-(H5-10{slash}SS'-Pad24)") (class "Default")
      (node (ref "H5") (pin "24") (pinfunction "10/SS'_24") (pintype "passive"))
    )
    (net (code "135") (name "unconnected-(H5-15{slash}A1-Pad19)") (class "Default")
      (node (ref "H5") (pin "19") (pinfunction "15/A1_19") (pintype "passive"))
    )
    (net (code "136") (name "unconnected-(H5-16{slash}A2-Pad18)") (class "Default")
      (node (ref "H5") (pin "18") (pinfunction "16/A2_18") (pintype "passive"))
    )
    (net (code "137") (name "unconnected-(H5-17{slash}A3-Pad17)") (class "Default")
      (node (ref "H5") (pin "17") (pinfunction "17/A3_17") (pintype "passive"))
    )
    (net (code "138") (name "unconnected-(H5-RAW-Pad13)") (class "Default")
      (node (ref "H5") (pin "13") (pinfunction "RAW_13") (pintype "passive"))
    )
    (net (code "139") (name "unconnected-(H5-RESET-Pad3)") (class "Default")
      (node (ref "H5") (pin "3") (pinfunction "RESET_3") (pintype "passive"))
    )
    (net (code "140") (name "unconnected-(H5-RESET-Pad15)") (class "Default")
      (node (ref "H5") (pin "15") (pinfunction "RESET_15") (pintype "passive"))
    )
    (net (code "141") (name "unconnected-(H6-DRDY-Pad5)") (class "Default")
      (node (ref "H6") (pin "5") (pinfunction "DRDY_5") (pintype "passive"))
    )
    (net (code "142") (name "unconnected-(H7-CS-Pad6)") (class "Default")
      (node (ref "H7") (pin "6") (pinfunction "CS_6") (pintype "passive"))
    )
    (net (code "143") (name "unconnected-(H7-DEN-Pad9)") (class "Default")
      (node (ref "H7") (pin "9") (pinfunction "DEN_9") (pintype "passive"))
    )
    (net (code "144") (name "unconnected-(H7-SD0-Pad5)") (class "Default")
      (node (ref "H7") (pin "5") (pinfunction "SD0_5") (pintype "passive"))
    )
    (net (code "145") (name "unconnected-(H7-T1-Pad8)") (class "Default")
      (node (ref "H7") (pin "8") (pinfunction "T1_8") (pintype "passive"))
    )
    (net (code "146") (name "unconnected-(H7-T2-Pad7)") (class "Default")
      (node (ref "H7") (pin "7") (pinfunction "T2_7") (pintype "passive"))
    )
  )
)
